# FA3D_Prelim.net
KiCad netlist of a schematic drawn in EAGLE
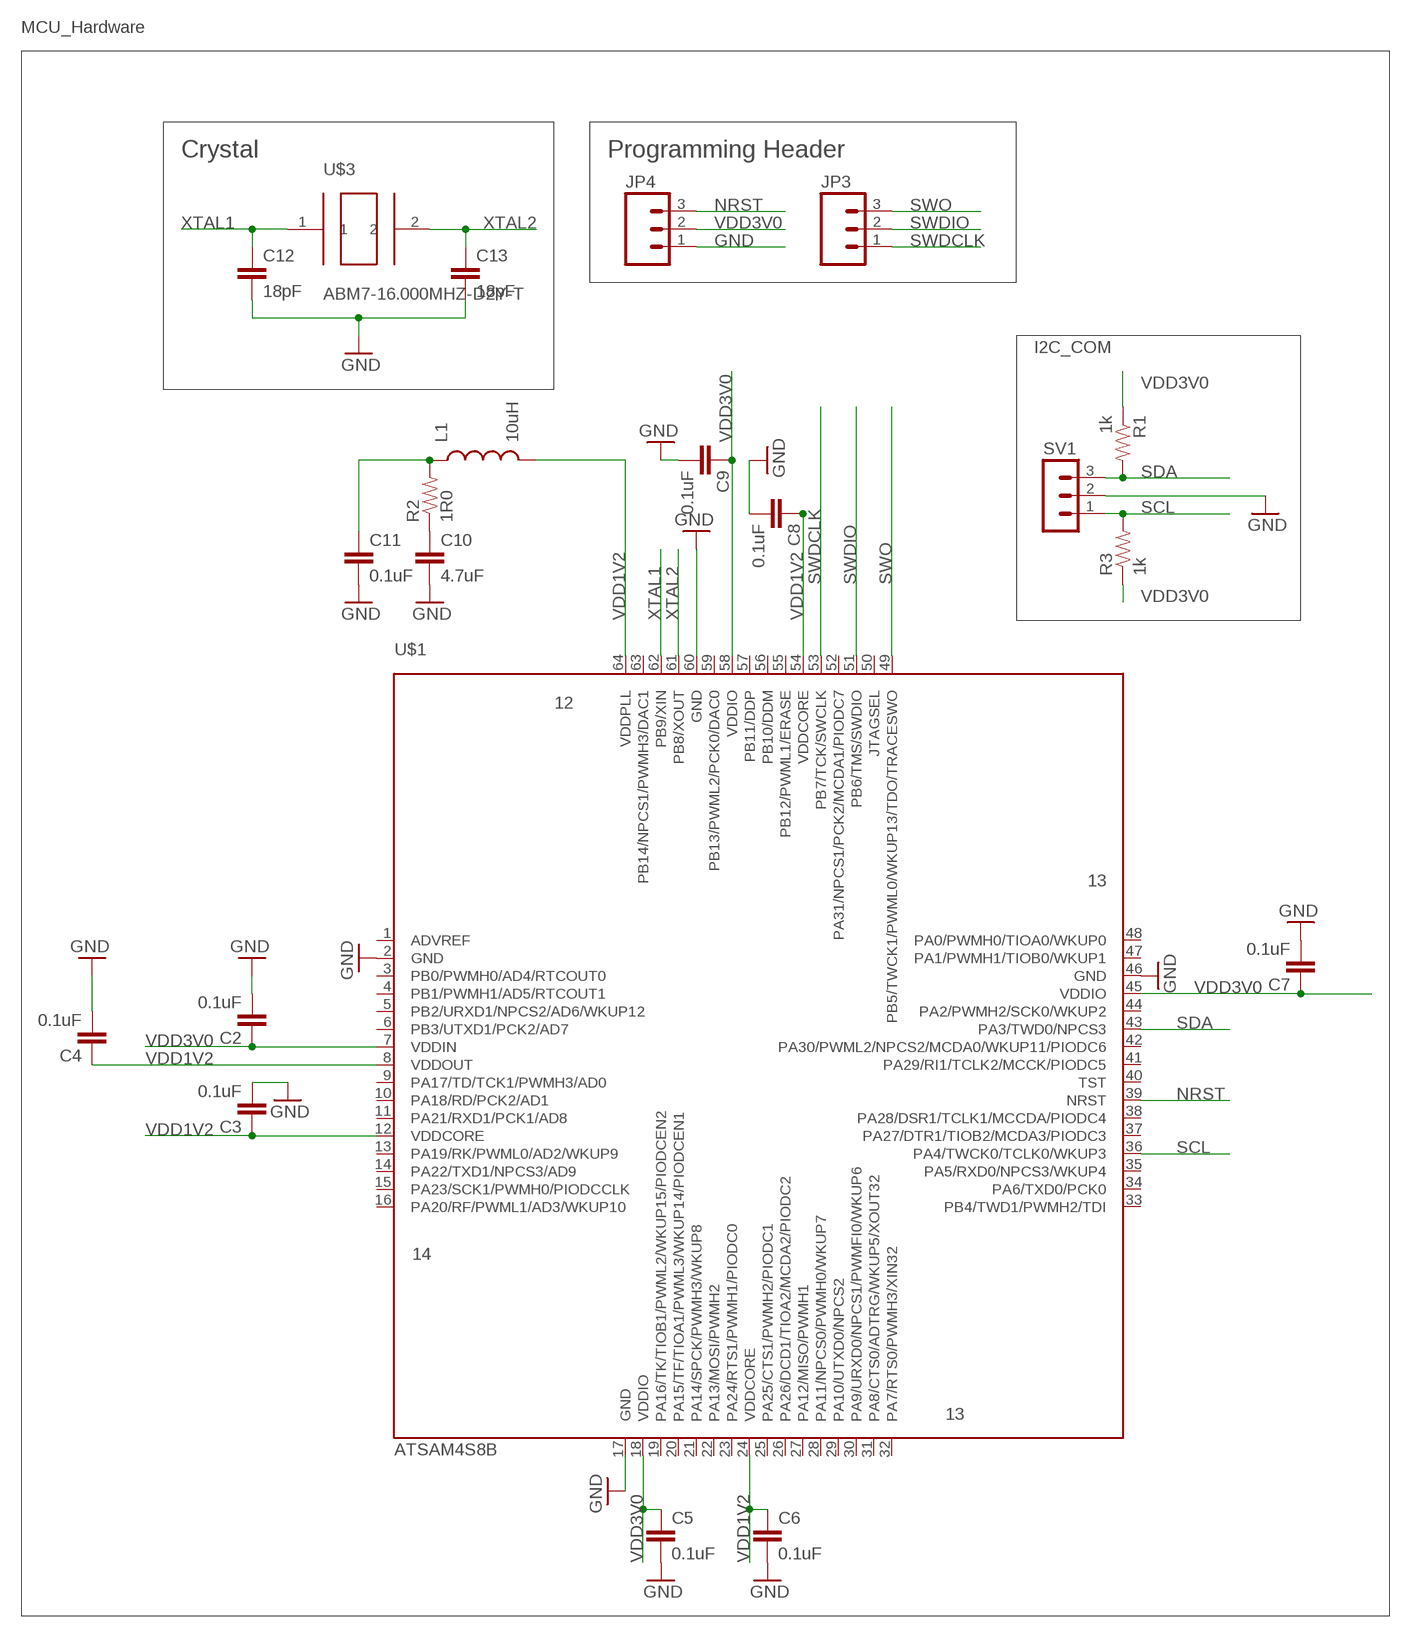
[diagram p0: schematic, sheet 1]

(export (version "E")
  (design (tool "Eeschema 10.0.6"))
  (components
    (comp (ref "C2")
      (value "0.1uF")
      (footprint "eagle-import:0805")
      (libsource (lib "eagle-import") (part "CAP0805"))
    )
    (comp (ref "C3")
      (value "0.1uF")
      (footprint "eagle-import:0805")
      (libsource (lib "eagle-import") (part "CAP0805"))
    )
    (comp (ref "C4")
      (value "0.1uF")
      (footprint "eagle-import:0805")
      (libsource (lib "eagle-import") (part "CAP0805"))
    )
    (comp (ref "C5")
      (value "0.1uF")
      (footprint "eagle-import:0805")
      (libsource (lib "eagle-import") (part "CAP0805"))
    )
    (comp (ref "C6")
      (value "0.1uF")
      (footprint "eagle-import:0805")
      (libsource (lib "eagle-import") (part "CAP0805"))
    )
    (comp (ref "C7")
      (value "0.1uF")
      (footprint "eagle-import:0805")
      (libsource (lib "eagle-import") (part "CAP0805"))
    )
    (comp (ref "C8")
      (value "0.1uF")
      (footprint "eagle-import:0805")
      (libsource (lib "eagle-import") (part "CAP0805"))
    )
    (comp (ref "C9")
      (value "0.1uF")
      (footprint "eagle-import:0805")
      (libsource (lib "eagle-import") (part "CAP0805"))
    )
    (comp (ref "C10")
      (value "4.7uF")
      (footprint "eagle-import:0805")
      (libsource (lib "eagle-import") (part "CAP0805"))
    )
    (comp (ref "C11")
      (value "0.1uF")
      (footprint "eagle-import:0805")
      (libsource (lib "eagle-import") (part "CAP0805"))
    )
    (comp (ref "C12")
      (value "18pF")
      (footprint "eagle-import:0805")
      (libsource (lib "eagle-import") (part "CAP0805"))
    )
    (comp (ref "C13")
      (value "18pF")
      (footprint "eagle-import:0805")
      (libsource (lib "eagle-import") (part "CAP0805"))
    )
    (comp (ref "JP3")
      (value "M03PTH")
      (footprint "eagle-import:1X03")
      (libsource (lib "eagle-import") (part "M03PTH"))
    )
    (comp (ref "JP4")
      (value "M03PTH")
      (footprint "eagle-import:1X03")
      (libsource (lib "eagle-import") (part "M03PTH"))
    )
    (comp (ref "L1")
      (value "10uH")
      (footprint "eagle-import:0805")
      (libsource (lib "eagle-import") (part "INDUCTOR0805"))
    )
    (comp (ref "R1")
      (value "1k")
      (footprint "eagle-import:0805")
      (libsource (lib "eagle-import") (part "RESISTOR0805-RES"))
    )
    (comp (ref "R2")
      (value "1R0")
      (footprint "eagle-import:0805")
      (libsource (lib "eagle-import") (part "RESISTOR0805-RES"))
    )
    (comp (ref "R3")
      (value "1k")
      (footprint "eagle-import:0805")
      (libsource (lib "eagle-import") (part "RESISTOR0805-RES"))
    )
    (comp (ref "SV1")
      (value "MA03-1")
      (footprint "eagle-import:MA03-1")
      (libsource (lib "eagle-import") (part "MA03-1"))
    )
    (comp (ref "U$1")
      (value "ATSAM4S8B")
      (footprint "eagle-import:QFP50P1200X1200X160-64N")
      (libsource (lib "eagle-import") (part "ATSAM4S8B"))
    )
    (comp (ref "U$3")
      (value "ABM7-16.000MHZ-D2Y-T")
      (footprint "eagle-import:ABM7-16.000MHZ-D2Y-T")
      (libsource (lib "eagle-import") (part "ABM7-16.000MHZ-D2Y-T"))
    )
  )
  (nets
    (net (code "1") (name "GND") (class "Default")
      (node (ref "C10") (pin "2") (pinfunction "2_2") (pintype "passive"))
      (node (ref "C11") (pin "2") (pinfunction "2_2") (pintype "passive"))
      (node (ref "C12") (pin "2") (pinfunction "2_2") (pintype "passive"))
      (node (ref "C13") (pin "2") (pinfunction "2_2") (pintype "passive"))
      (node (ref "C2") (pin "2") (pinfunction "2_2") (pintype "passive"))
      (node (ref "C3") (pin "2") (pinfunction "2_2") (pintype "passive"))
      (node (ref "C4") (pin "2") (pinfunction "2_2") (pintype "passive"))
      (node (ref "C5") (pin "2") (pinfunction "2_2") (pintype "passive"))
      (node (ref "C6") (pin "2") (pinfunction "2_2") (pintype "passive"))
      (node (ref "C7") (pin "2") (pinfunction "2_2") (pintype "passive"))
      (node (ref "C8") (pin "2") (pinfunction "2_2") (pintype "passive"))
      (node (ref "C9") (pin "2") (pinfunction "2_2") (pintype "passive"))
      (node (ref "JP4") (pin "1") (pinfunction "1_1") (pintype "passive"))
      (node (ref "SV1") (pin "2") (pinfunction "2_2") (pintype "passive"))
      (node (ref "U$1") (pin "17") (pinfunction "GND_17") (pintype "bidirectional"))
      (node (ref "U$1") (pin "2") (pinfunction "GND_2") (pintype "bidirectional"))
      (node (ref "U$1") (pin "46") (pinfunction "GND_46") (pintype "bidirectional"))
      (node (ref "U$1") (pin "60") (pinfunction "GND_60") (pintype "bidirectional"))
    )
    (net (code "2") (name "NRST") (class "Default")
      (node (ref "JP4") (pin "3") (pinfunction "3_3") (pintype "passive"))
      (node (ref "U$1") (pin "39") (pinfunction "NRST_39") (pintype "bidirectional"))
    )
    (net (code "3") (name "Net-(C10-Pad1)") (class "Default")
      (node (ref "C10") (pin "1") (pinfunction "1_1") (pintype "passive"))
      (node (ref "R2") (pin "1") (pinfunction "1_1") (pintype "passive"))
    )
    (net (code "4") (name "Net-(C11-Pad1)") (class "Default")
      (node (ref "C11") (pin "1") (pinfunction "1_1") (pintype "passive"))
      (node (ref "L1") (pin "1") (pinfunction "1_1") (pintype "passive"))
      (node (ref "R2") (pin "2") (pinfunction "2_2") (pintype "passive"))
    )
    (net (code "5") (name "SCL") (class "Default")
      (node (ref "R3") (pin "2") (pinfunction "2_2") (pintype "passive"))
      (node (ref "SV1") (pin "1") (pinfunction "1_1") (pintype "passive"))
      (node (ref "U$1") (pin "36") (pinfunction "PA4/TWCK0/TCLK0/WKUP3_36") (pintype "bidirectional"))
    )
    (net (code "6") (name "SDA") (class "Default")
      (node (ref "R1") (pin "2") (pinfunction "2_2") (pintype "passive"))
      (node (ref "SV1") (pin "3") (pinfunction "3_3") (pintype "passive"))
      (node (ref "U$1") (pin "43") (pinfunction "PA3/TWD0/NPCS3_43") (pintype "bidirectional"))
    )
    (net (code "7") (name "SWDCLK") (class "Default")
      (node (ref "JP3") (pin "1") (pinfunction "1_1") (pintype "passive"))
      (node (ref "U$1") (pin "53") (pinfunction "PB7/TCK/SWCLK_53") (pintype "bidirectional"))
    )
    (net (code "8") (name "SWDIO") (class "Default")
      (node (ref "JP3") (pin "2") (pinfunction "2_2") (pintype "passive"))
      (node (ref "U$1") (pin "51") (pinfunction "PB6/TMS/SWDIO_51") (pintype "bidirectional"))
    )
    (net (code "9") (name "SWO") (class "Default")
      (node (ref "JP3") (pin "3") (pinfunction "3_3") (pintype "passive"))
      (node (ref "U$1") (pin "49") (pinfunction "PB5/TWCK1/PWML0/WKUP13/TDO/TRACESWO_49") (pintype "bidirectional"))
    )
    (net (code "10") (name "VDD1V2") (class "Default")
      (node (ref "C3") (pin "1") (pinfunction "1_1") (pintype "passive"))
      (node (ref "C4") (pin "1") (pinfunction "1_1") (pintype "passive"))
      (node (ref "C6") (pin "1") (pinfunction "1_1") (pintype "passive"))
      (node (ref "C8") (pin "1") (pinfunction "1_1") (pintype "passive"))
      (node (ref "L1") (pin "2") (pinfunction "2_2") (pintype "passive"))
      (node (ref "U$1") (pin "12") (pinfunction "VDDCORE_12") (pintype "bidirectional"))
      (node (ref "U$1") (pin "24") (pinfunction "VDDCORE_24") (pintype "bidirectional"))
      (node (ref "U$1") (pin "54") (pinfunction "VDDCORE_54") (pintype "bidirectional"))
      (node (ref "U$1") (pin "64") (pinfunction "VDDPLL_64") (pintype "bidirectional"))
      (node (ref "U$1") (pin "8") (pinfunction "VDDOUT_8") (pintype "bidirectional"))
    )
    (net (code "11") (name "VDD3V0") (class "Default")
      (node (ref "C2") (pin "1") (pinfunction "1_1") (pintype "passive"))
      (node (ref "C5") (pin "1") (pinfunction "1_1") (pintype "passive"))
      (node (ref "C7") (pin "1") (pinfunction "1_1") (pintype "passive"))
      (node (ref "C9") (pin "1") (pinfunction "1_1") (pintype "passive"))
      (node (ref "JP4") (pin "2") (pinfunction "2_2") (pintype "passive"))
      (node (ref "R1") (pin "1") (pinfunction "1_1") (pintype "passive"))
      (node (ref "R3") (pin "1") (pinfunction "1_1") (pintype "passive"))
      (node (ref "U$1") (pin "18") (pinfunction "VDDIO_18") (pintype "bidirectional"))
      (node (ref "U$1") (pin "45") (pinfunction "VDDIO_45") (pintype "bidirectional"))
      (node (ref "U$1") (pin "58") (pinfunction "VDDIO_58") (pintype "bidirectional"))
      (node (ref "U$1") (pin "7") (pinfunction "VDDIN_7") (pintype "bidirectional"))
    )
    (net (code "12") (name "XTAL1") (class "Default")
      (node (ref "C12") (pin "1") (pinfunction "1_1") (pintype "passive"))
      (node (ref "U$1") (pin "62") (pinfunction "PB9/XIN_62") (pintype "bidirectional"))
      (node (ref "U$3") (pin "1") (pinfunction "1_1") (pintype "bidirectional"))
    )
    (net (code "13") (name "XTAL2") (class "Default")
      (node (ref "C13") (pin "1") (pinfunction "1_1") (pintype "passive"))
      (node (ref "U$1") (pin "61") (pinfunction "PB8/XOUT_61") (pintype "bidirectional"))
      (node (ref "U$3") (pin "2") (pinfunction "2_2") (pintype "bidirectional"))
    )
    (net (code "14") (name "unconnected-(U$1-ADVREF-Pad1)") (class "Default")
      (node (ref "U$1") (pin "1") (pinfunction "ADVREF_1") (pintype "bidirectional"))
    )
    (net (code "15") (name "unconnected-(U$1-JTAGSEL-Pad50)") (class "Default")
      (node (ref "U$1") (pin "50") (pinfunction "JTAGSEL_50") (pintype "bidirectional"))
    )
    (net (code "16") (name "unconnected-(U$1-PA0{slash}PWMH0{slash}TIOA0{slash}WKUP0-Pad48)") (class "Default")
      (node (ref "U$1") (pin "48") (pinfunction "PA0/PWMH0/TIOA0/WKUP0_48") (pintype "bidirectional"))
    )
    (net (code "17") (name "unconnected-(U$1-PA1{slash}PWMH1{slash}TIOB0{slash}WKUP1-Pad47)") (class "Default")
      (node (ref "U$1") (pin "47") (pinfunction "PA1/PWMH1/TIOB0/WKUP1_47") (pintype "bidirectional"))
    )
    (net (code "18") (name "unconnected-(U$1-PA2{slash}PWMH2{slash}SCK0{slash}WKUP2-Pad44)") (class "Default")
      (node (ref "U$1") (pin "44") (pinfunction "PA2/PWMH2/SCK0/WKUP2_44") (pintype "bidirectional"))
    )
    (net (code "19") (name "unconnected-(U$1-PA5{slash}RXD0{slash}NPCS3{slash}WKUP4-Pad35)") (class "Default")
      (node (ref "U$1") (pin "35") (pinfunction "PA5/RXD0/NPCS3/WKUP4_35") (pintype "bidirectional"))
    )
    (net (code "20") (name "unconnected-(U$1-PA6{slash}TXD0{slash}PCK0-Pad34)") (class "Default")
      (node (ref "U$1") (pin "34") (pinfunction "PA6/TXD0/PCK0_34") (pintype "bidirectional"))
    )
    (net (code "21") (name "unconnected-(U$1-PA7{slash}RTS0{slash}PWMH3{slash}XIN32-Pad32)") (class "Default")
      (node (ref "U$1") (pin "32") (pinfunction "PA7/RTS0/PWMH3/XIN32_32") (pintype "bidirectional"))
    )
    (net (code "22") (name "unconnected-(U$1-PA8{slash}CTS0{slash}ADTRG{slash}WKUP5{slash}XOUT32-Pad31)") (class "Default")
      (node (ref "U$1") (pin "31") (pinfunction "PA8/CTS0/ADTRG/WKUP5/XOUT32_31") (pintype "bidirectional"))
    )
    (net (code "23") (name "unconnected-(U$1-PA9{slash}URXD0{slash}NPCS1{slash}PWMFI0{slash}WKUP6-Pad30)") (class "Default")
      (node (ref "U$1") (pin "30") (pinfunction "PA9/URXD0/NPCS1/PWMFI0/WKUP6_30") (pintype "bidirectional"))
    )
    (net (code "24") (name "unconnected-(U$1-PA10{slash}UTXD0{slash}NPCS2-Pad29)") (class "Default")
      (node (ref "U$1") (pin "29") (pinfunction "PA10/UTXD0/NPCS2_29") (pintype "bidirectional"))
    )
    (net (code "25") (name "unconnected-(U$1-PA11{slash}NPCS0{slash}PWMH0{slash}WKUP7-Pad28)") (class "Default")
      (node (ref "U$1") (pin "28") (pinfunction "PA11/NPCS0/PWMH0/WKUP7_28") (pintype "bidirectional"))
    )
    (net (code "26") (name "unconnected-(U$1-PA12{slash}MISO{slash}PWMH1-Pad27)") (class "Default")
      (node (ref "U$1") (pin "27") (pinfunction "PA12/MISO/PWMH1_27") (pintype "bidirectional"))
    )
    (net (code "27") (name "unconnected-(U$1-PA13{slash}MOSI{slash}PWMH2-Pad22)") (class "Default")
      (node (ref "U$1") (pin "22") (pinfunction "PA13/MOSI/PWMH2_22") (pintype "bidirectional"))
    )
    (net (code "28") (name "unconnected-(U$1-PA14{slash}SPCK{slash}PWMH3{slash}WKUP8-Pad21)") (class "Default")
      (node (ref "U$1") (pin "21") (pinfunction "PA14/SPCK/PWMH3/WKUP8_21") (pintype "bidirectional"))
    )
    (net (code "29") (name "unconnected-(U$1-PA15{slash}TF{slash}TIOA1{slash}PWML3{slash}WKUP14{slash}PIODCEN1-Pad20)") (class "Default")
      (node (ref "U$1") (pin "20") (pinfunction "PA15/TF/TIOA1/PWML3/WKUP14/PIODCEN1_20") (pintype "bidirectional"))
    )
    (net (code "30") (name "unconnected-(U$1-PA16{slash}TK{slash}TIOB1{slash}PWML2{slash}WKUP15{slash}PIODCEN2-Pad19)") (class "Default")
      (node (ref "U$1") (pin "19") (pinfunction "PA16/TK/TIOB1/PWML2/WKUP15/PIODCEN2_19") (pintype "bidirectional"))
    )
    (net (code "31") (name "unconnected-(U$1-PA17{slash}TD{slash}TCK1{slash}PWMH3{slash}AD0-Pad9)") (class "Default")
      (node (ref "U$1") (pin "9") (pinfunction "PA17/TD/TCK1/PWMH3/AD0_9") (pintype "bidirectional"))
    )
    (net (code "32") (name "unconnected-(U$1-PA18{slash}RD{slash}PCK2{slash}AD1-Pad10)") (class "Default")
      (node (ref "U$1") (pin "10") (pinfunction "PA18/RD/PCK2/AD1_10") (pintype "bidirectional"))
    )
    (net (code "33") (name "unconnected-(U$1-PA19{slash}RK{slash}PWML0{slash}AD2{slash}WKUP9-Pad13)") (class "Default")
      (node (ref "U$1") (pin "13") (pinfunction "PA19/RK/PWML0/AD2/WKUP9_13") (pintype "bidirectional"))
    )
    (net (code "34") (name "unconnected-(U$1-PA20{slash}RF{slash}PWML1{slash}AD3{slash}WKUP10-Pad16)") (class "Default")
      (node (ref "U$1") (pin "16") (pinfunction "PA20/RF/PWML1/AD3/WKUP10_16") (pintype "bidirectional"))
    )
    (net (code "35") (name "unconnected-(U$1-PA21{slash}RXD1{slash}PCK1{slash}AD8-Pad11)") (class "Default")
      (node (ref "U$1") (pin "11") (pinfunction "PA21/RXD1/PCK1/AD8_11") (pintype "bidirectional"))
    )
    (net (code "36") (name "unconnected-(U$1-PA22{slash}TXD1{slash}NPCS3{slash}AD9-Pad14)") (class "Default")
      (node (ref "U$1") (pin "14") (pinfunction "PA22/TXD1/NPCS3/AD9_14") (pintype "bidirectional"))
    )
    (net (code "37") (name "unconnected-(U$1-PA23{slash}SCK1{slash}PWMH0{slash}PIODCCLK-Pad15)") (class "Default")
      (node (ref "U$1") (pin "15") (pinfunction "PA23/SCK1/PWMH0/PIODCCLK_15") (pintype "bidirectional"))
    )
    (net (code "38") (name "unconnected-(U$1-PA24{slash}RTS1{slash}PWMH1{slash}PIODC0-Pad23)") (class "Default")
      (node (ref "U$1") (pin "23") (pinfunction "PA24/RTS1/PWMH1/PIODC0_23") (pintype "bidirectional"))
    )
    (net (code "39") (name "unconnected-(U$1-PA25{slash}CTS1{slash}PWMH2{slash}PIODC1-Pad25)") (class "Default")
      (node (ref "U$1") (pin "25") (pinfunction "PA25/CTS1/PWMH2/PIODC1_25") (pintype "bidirectional"))
    )
    (net (code "40") (name "unconnected-(U$1-PA26{slash}DCD1{slash}TIOA2{slash}MCDA2{slash}PIODC2-Pad26)") (class "Default")
      (node (ref "U$1") (pin "26") (pinfunction "PA26/DCD1/TIOA2/MCDA2/PIODC2_26") (pintype "bidirectional"))
    )
    (net (code "41") (name "unconnected-(U$1-PA27{slash}DTR1{slash}TIOB2{slash}MCDA3{slash}PIODC3-Pad37)") (class "Default")
      (node (ref "U$1") (pin "37") (pinfunction "PA27/DTR1/TIOB2/MCDA3/PIODC3_37") (pintype "bidirectional"))
    )
    (net (code "42") (name "unconnected-(U$1-PA28{slash}DSR1{slash}TCLK1{slash}MCCDA{slash}PIODC4-Pad38)") (class "Default")
      (node (ref "U$1") (pin "38") (pinfunction "PA28/DSR1/TCLK1/MCCDA/PIODC4_38") (pintype "bidirectional"))
    )
    (net (code "43") (name "unconnected-(U$1-PA29{slash}RI1{slash}TCLK2{slash}MCCK{slash}PIODC5-Pad41)") (class "Default")
      (node (ref "U$1") (pin "41") (pinfunction "PA29/RI1/TCLK2/MCCK/PIODC5_41") (pintype "bidirectional"))
    )
    (net (code "44") (name "unconnected-(U$1-PA30{slash}PWML2{slash}NPCS2{slash}MCDA0{slash}WKUP11{slash}PIODC6-Pad42)") (class "Default")
      (node (ref "U$1") (pin "42") (pinfunction "PA30/PWML2/NPCS2/MCDA0/WKUP11/PIODC6_42") (pintype "bidirectional"))
    )
    (net (code "45") (name "unconnected-(U$1-PA31{slash}NPCS1{slash}PCK2{slash}MCDA1{slash}PIODC7-Pad52)") (class "Default")
      (node (ref "U$1") (pin "52") (pinfunction "PA31/NPCS1/PCK2/MCDA1/PIODC7_52") (pintype "bidirectional"))
    )
    (net (code "46") (name "unconnected-(U$1-PB0{slash}PWMH0{slash}AD4{slash}RTCOUT0-Pad3)") (class "Default")
      (node (ref "U$1") (pin "3") (pinfunction "PB0/PWMH0/AD4/RTCOUT0_3") (pintype "bidirectional"))
    )
    (net (code "47") (name "unconnected-(U$1-PB1{slash}PWMH1{slash}AD5{slash}RTCOUT1-Pad4)") (class "Default")
      (node (ref "U$1") (pin "4") (pinfunction "PB1/PWMH1/AD5/RTCOUT1_4") (pintype "bidirectional"))
    )
    (net (code "48") (name "unconnected-(U$1-PB2{slash}URXD1{slash}NPCS2{slash}AD6{slash}WKUP12-Pad5)") (class "Default")
      (node (ref "U$1") (pin "5") (pinfunction "PB2/URXD1/NPCS2/AD6/WKUP12_5") (pintype "bidirectional"))
    )
    (net (code "49") (name "unconnected-(U$1-PB3{slash}UTXD1{slash}PCK2{slash}AD7-Pad6)") (class "Default")
      (node (ref "U$1") (pin "6") (pinfunction "PB3/UTXD1/PCK2/AD7_6") (pintype "bidirectional"))
    )
    (net (code "50") (name "unconnected-(U$1-PB4{slash}TWD1{slash}PWMH2{slash}TDI-Pad33)") (class "Default")
      (node (ref "U$1") (pin "33") (pinfunction "PB4/TWD1/PWMH2/TDI_33") (pintype "bidirectional"))
    )
    (net (code "51") (name "unconnected-(U$1-PB10{slash}DDM-Pad56)") (class "Default")
      (node (ref "U$1") (pin "56") (pinfunction "PB10/DDM_56") (pintype "bidirectional"))
    )
    (net (code "52") (name "unconnected-(U$1-PB11{slash}DDP-Pad57)") (class "Default")
      (node (ref "U$1") (pin "57") (pinfunction "PB11/DDP_57") (pintype "bidirectional"))
    )
    (net (code "53") (name "unconnected-(U$1-PB12{slash}PWML1{slash}ERASE-Pad55)") (class "Default")
      (node (ref "U$1") (pin "55") (pinfunction "PB12/PWML1/ERASE_55") (pintype "bidirectional"))
    )
    (net (code "54") (name "unconnected-(U$1-PB13{slash}PWML2{slash}PCK0{slash}DAC0-Pad59)") (class "Default")
      (node (ref "U$1") (pin "59") (pinfunction "PB13/PWML2/PCK0/DAC0_59") (pintype "bidirectional"))
    )
    (net (code "55") (name "unconnected-(U$1-PB14{slash}NPCS1{slash}PWMH3{slash}DAC1-Pad63)") (class "Default")
      (node (ref "U$1") (pin "63") (pinfunction "PB14/NPCS1/PWMH3/DAC1_63") (pintype "bidirectional"))
    )
    (net (code "56") (name "unconnected-(U$1-TST-Pad40)") (class "Default")
      (node (ref "U$1") (pin "40") (pinfunction "TST_40") (pintype "bidirectional"))
    )
  )
)
